# BLOCK3.net
KiCad netlist of a schematic drawn in Altium Designer
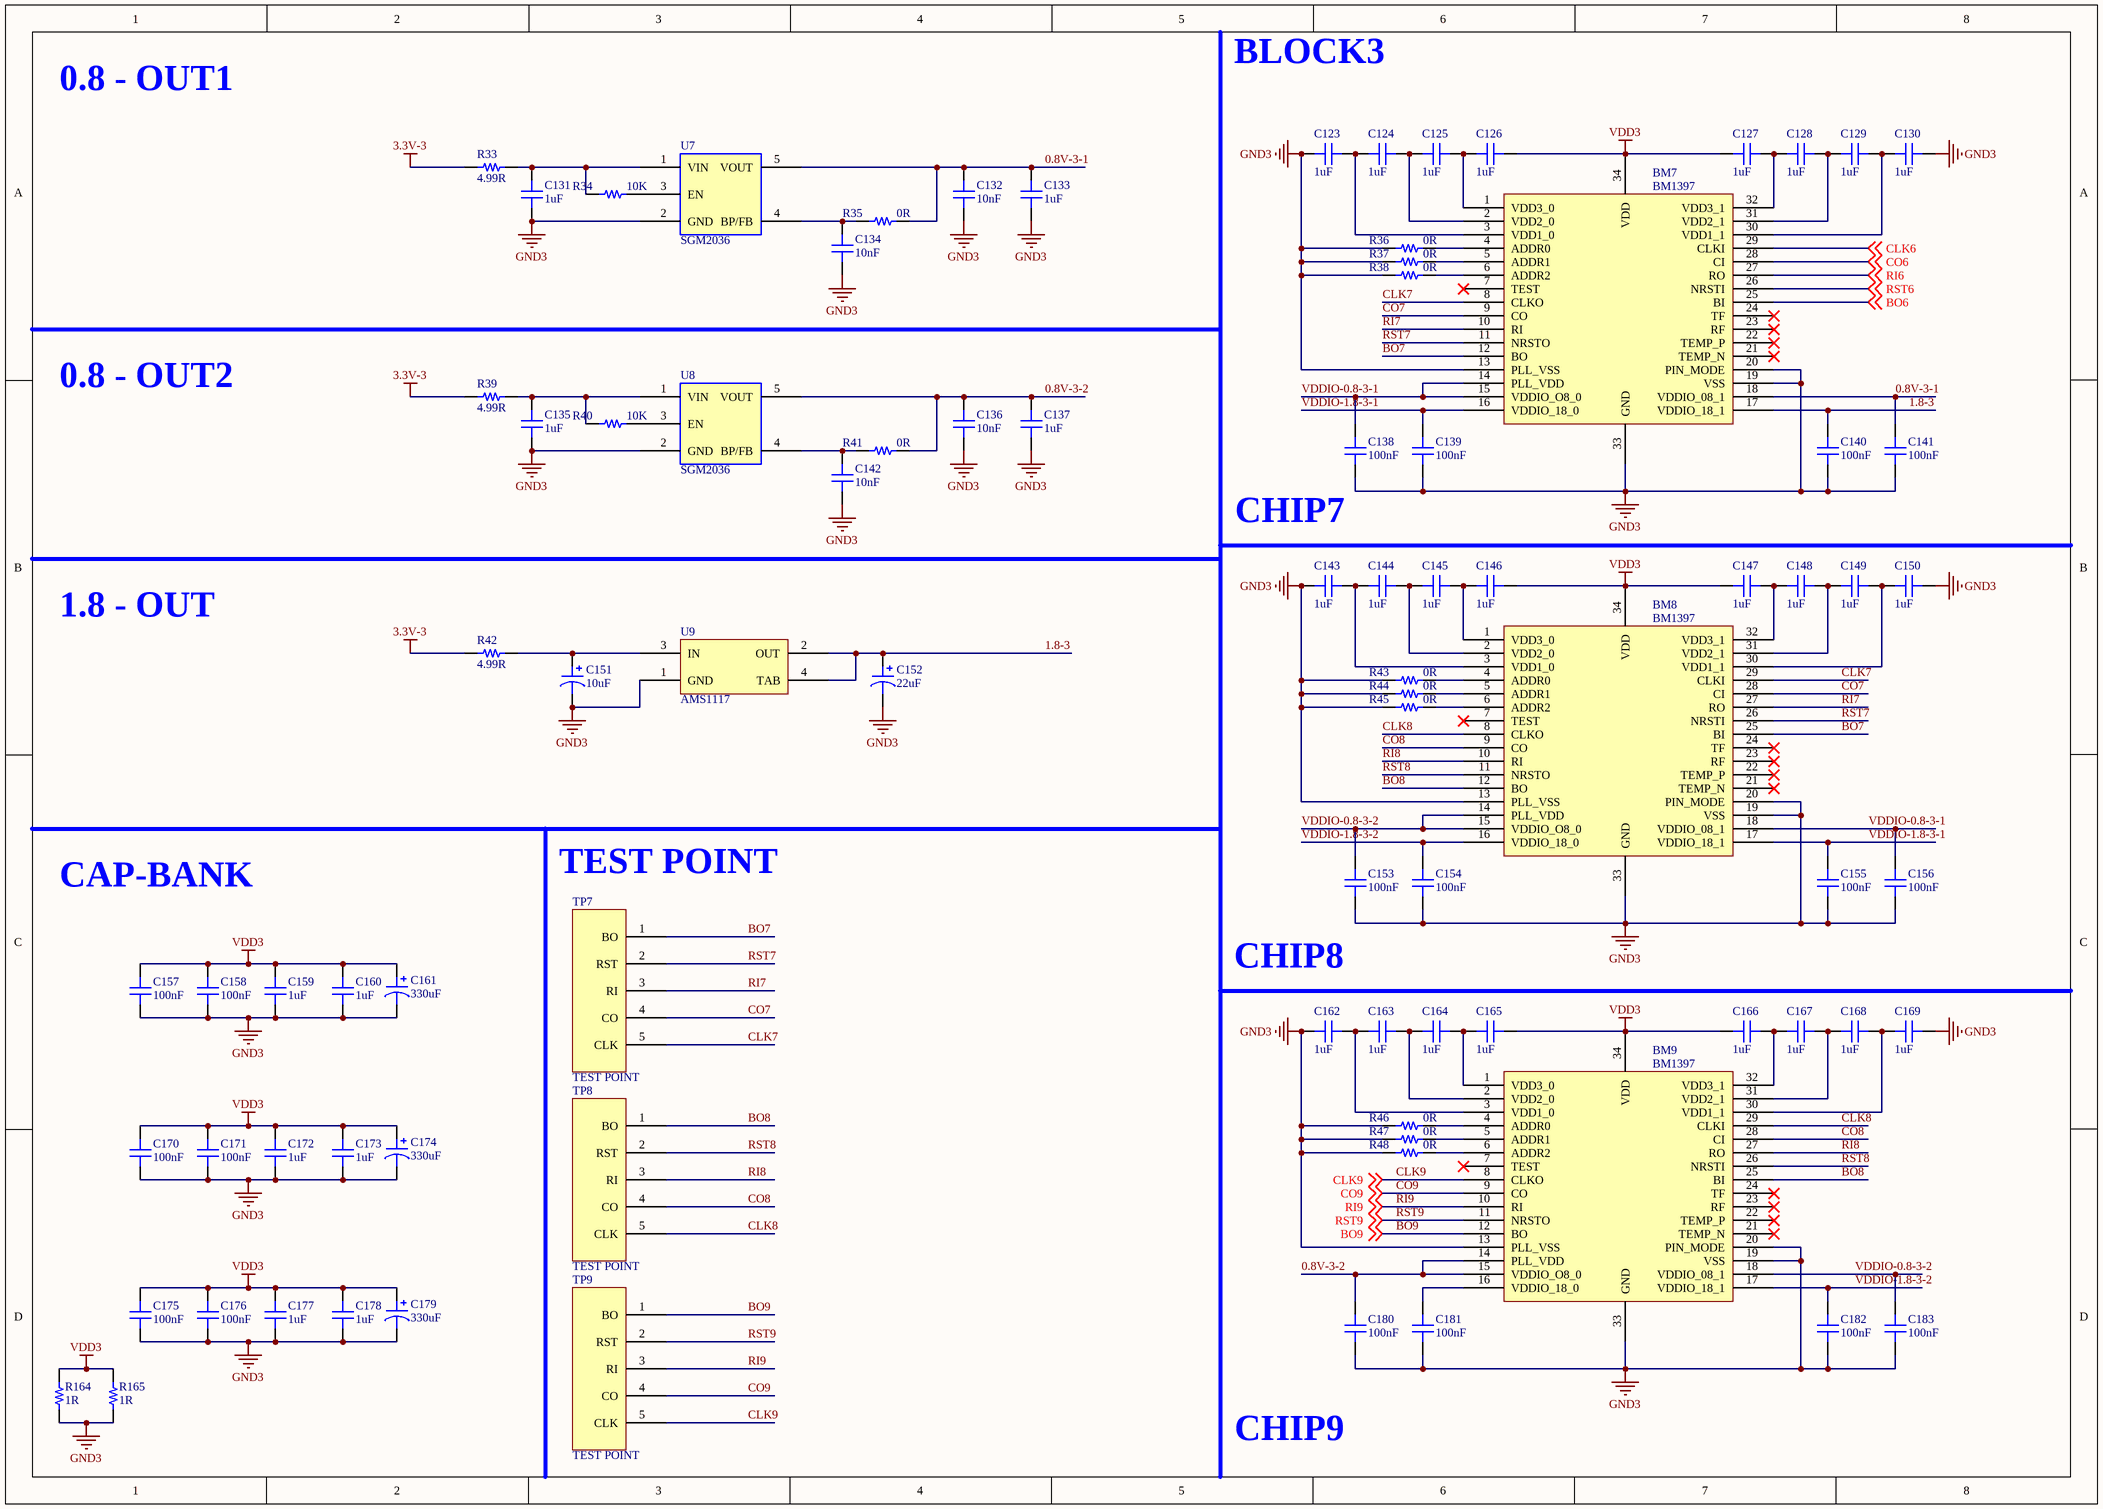
[diagram p0: BLOCK3.SchDoc]

(export (version "E")
  (design (tool "Eeschema 10.0.6"))
  (components
    (comp (ref "BM7") (value "BM1397") (footprint "BM1387") (libsource (lib "Miner_8TH") (part "BM1397_0")))
    (comp (ref "BM8") (value "BM1397") (footprint "BM1387") (libsource (lib "Miner_8TH") (part "BM1397_0")))
    (comp (ref "BM9") (value "BM1397") (footprint "BM1387") (libsource (lib "Miner_8TH") (part "BM1397_0")))
    (comp (ref "C123") (value "1uF") (footprint "CAP-SMD-0603") (libsource (lib "Miner_8TH") (part "CAP")))
    (comp (ref "C124") (value "1uF") (footprint "CAP-SMD-0603") (libsource (lib "Miner_8TH") (part "CAP")))
    (comp (ref "C125") (value "1uF") (footprint "CAP-SMD-0603") (libsource (lib "Miner_8TH") (part "CAP")))
    (comp (ref "C126") (value "1uF") (footprint "CAP-SMD-0603") (libsource (lib "Miner_8TH") (part "CAP")))
    (comp (ref "C127") (value "1uF") (footprint "CAP-SMD-0603") (libsource (lib "Miner_8TH") (part "CAP")))
    (comp (ref "C128") (value "1uF") (footprint "CAP-SMD-0603") (libsource (lib "Miner_8TH") (part "CAP")))
    (comp (ref "C129") (value "1uF") (footprint "CAP-SMD-0603") (libsource (lib "Miner_8TH") (part "CAP")))
    (comp (ref "C130") (value "1uF") (footprint "CAP-SMD-0603") (libsource (lib "Miner_8TH") (part "CAP")))
    (comp (ref "C131") (value "1uF") (footprint "CAP_SMD_0805") (libsource (lib "Miner_8TH") (part "CAP")))
    (comp (ref "C132") (value "10nF") (footprint "CAP_SMD_0805") (libsource (lib "Miner_8TH") (part "CAP")))
    (comp (ref "C133") (value "1uF") (footprint "CAP_SMD_0805") (libsource (lib "Miner_8TH") (part "CAP")))
    (comp (ref "C134") (value "10nF") (footprint "CAP_SMD_0805") (libsource (lib "Miner_8TH") (part "CAP")))
    (comp (ref "C135") (value "1uF") (footprint "CAP_SMD_0805") (libsource (lib "Miner_8TH") (part "CAP")))
    (comp (ref "C136") (value "10nF") (footprint "CAP_SMD_0805") (libsource (lib "Miner_8TH") (part "CAP")))
    (comp (ref "C137") (value "1uF") (footprint "CAP_SMD_0805") (libsource (lib "Miner_8TH") (part "CAP")))
    (comp (ref "C138") (value "100nF") (footprint "CAP_SMD_0805") (libsource (lib "Miner_8TH") (part "CAP")))
    (comp (ref "C139") (value "100nF") (footprint "CAP_SMD_0805") (libsource (lib "Miner_8TH") (part "CAP")))
    (comp (ref "C140") (value "100nF") (footprint "CAP_SMD_0805") (libsource (lib "Miner_8TH") (part "CAP")))
    (comp (ref "C141") (value "100nF") (footprint "CAP_SMD_0805") (libsource (lib "Miner_8TH") (part "CAP")))
    (comp (ref "C142") (value "10nF") (footprint "CAP_SMD_0805") (libsource (lib "Miner_8TH") (part "CAP")))
    (comp (ref "C143") (value "1uF") (footprint "CAP-SMD-0603") (libsource (lib "Miner_8TH") (part "CAP")))
    (comp (ref "C144") (value "1uF") (footprint "CAP-SMD-0603") (libsource (lib "Miner_8TH") (part "CAP")))
    (comp (ref "C145") (value "1uF") (footprint "CAP-SMD-0603") (libsource (lib "Miner_8TH") (part "CAP")))
    (comp (ref "C146") (value "1uF") (footprint "CAP-SMD-0603") (libsource (lib "Miner_8TH") (part "CAP")))
    (comp (ref "C147") (value "1uF") (footprint "CAP-SMD-0603") (libsource (lib "Miner_8TH") (part "CAP")))
    (comp (ref "C148") (value "1uF") (footprint "CAP-SMD-0603") (libsource (lib "Miner_8TH") (part "CAP")))
    (comp (ref "C149") (value "1uF") (footprint "CAP-SMD-0603") (libsource (lib "Miner_8TH") (part "CAP")))
    (comp (ref "C150") (value "1uF") (footprint "CAP-SMD-0603") (libsource (lib "Miner_8TH") (part "CAP")))
    (comp (ref "C151")
      (value "10uF")
      (footprint "CAP-TAN-CASE-A")
      (libsource (lib "Miner_8TH") (part "POLARIZED CAP"))
    )
    (comp (ref "C152")
      (value "22uF")
      (footprint "CAP-TAN-CASE-A")
      (libsource (lib "Miner_8TH") (part "POLARIZED CAP"))
    )
    (comp (ref "C153") (value "100nF") (footprint "CAP_SMD_0805") (libsource (lib "Miner_8TH") (part "CAP")))
    (comp (ref "C154") (value "100nF") (footprint "CAP_SMD_0805") (libsource (lib "Miner_8TH") (part "CAP")))
    (comp (ref "C155") (value "100nF") (footprint "CAP_SMD_0805") (libsource (lib "Miner_8TH") (part "CAP")))
    (comp (ref "C156") (value "100nF") (footprint "CAP_SMD_0805") (libsource (lib "Miner_8TH") (part "CAP")))
    (comp (ref "C157") (value "100nF") (footprint "CAP_SMD_0805") (libsource (lib "Miner_8TH") (part "CAP")))
    (comp (ref "C158") (value "100nF") (footprint "CAP_SMD_0805") (libsource (lib "Miner_8TH") (part "CAP")))
    (comp (ref "C159") (value "1uF") (footprint "CAP_SMD_0805") (libsource (lib "Miner_8TH") (part "CAP")))
    (comp (ref "C160") (value "1uF") (footprint "CAP_SMD_0805") (libsource (lib "Miner_8TH") (part "CAP")))
    (comp (ref "C161")
      (value "330uF")
      (footprint "CAP-TAN-CASE-E")
      (libsource (lib "Miner_8TH") (part "POLARIZED CAP"))
    )
    (comp (ref "C162") (value "1uF") (footprint "CAP-SMD-0603") (libsource (lib "Miner_8TH") (part "CAP")))
    (comp (ref "C163") (value "1uF") (footprint "CAP-SMD-0603") (libsource (lib "Miner_8TH") (part "CAP")))
    (comp (ref "C164") (value "1uF") (footprint "CAP-SMD-0603") (libsource (lib "Miner_8TH") (part "CAP")))
    (comp (ref "C165") (value "1uF") (footprint "CAP-SMD-0603") (libsource (lib "Miner_8TH") (part "CAP")))
    (comp (ref "C166") (value "1uF") (footprint "CAP-SMD-0603") (libsource (lib "Miner_8TH") (part "CAP")))
    (comp (ref "C167") (value "1uF") (footprint "CAP-SMD-0603") (libsource (lib "Miner_8TH") (part "CAP")))
    (comp (ref "C168") (value "1uF") (footprint "CAP-SMD-0603") (libsource (lib "Miner_8TH") (part "CAP")))
    (comp (ref "C169") (value "1uF") (footprint "CAP-SMD-0603") (libsource (lib "Miner_8TH") (part "CAP")))
    (comp (ref "C170") (value "100nF") (footprint "CAP_SMD_0805") (libsource (lib "Miner_8TH") (part "CAP")))
    (comp (ref "C171") (value "100nF") (footprint "CAP_SMD_0805") (libsource (lib "Miner_8TH") (part "CAP")))
    (comp (ref "C172") (value "1uF") (footprint "CAP_SMD_0805") (libsource (lib "Miner_8TH") (part "CAP")))
    (comp (ref "C173") (value "1uF") (footprint "CAP_SMD_0805") (libsource (lib "Miner_8TH") (part "CAP")))
    (comp (ref "C174")
      (value "330uF")
      (footprint "CAP-TAN-CASE-E")
      (libsource (lib "Miner_8TH") (part "POLARIZED CAP"))
    )
    (comp (ref "C175") (value "100nF") (footprint "CAP_SMD_0805") (libsource (lib "Miner_8TH") (part "CAP")))
    (comp (ref "C176") (value "100nF") (footprint "CAP_SMD_0805") (libsource (lib "Miner_8TH") (part "CAP")))
    (comp (ref "C177") (value "1uF") (footprint "CAP_SMD_0805") (libsource (lib "Miner_8TH") (part "CAP")))
    (comp (ref "C178") (value "1uF") (footprint "CAP_SMD_0805") (libsource (lib "Miner_8TH") (part "CAP")))
    (comp (ref "C179")
      (value "330uF")
      (footprint "CAP-TAN-CASE-E")
      (libsource (lib "Miner_8TH") (part "POLARIZED CAP"))
    )
    (comp (ref "C180") (value "100nF") (footprint "CAP_SMD_0805") (libsource (lib "Miner_8TH") (part "CAP")))
    (comp (ref "C181") (value "100nF") (footprint "CAP_SMD_0805") (libsource (lib "Miner_8TH") (part "CAP")))
    (comp (ref "C182") (value "100nF") (footprint "CAP_SMD_0805") (libsource (lib "Miner_8TH") (part "CAP")))
    (comp (ref "C183") (value "100nF") (footprint "CAP_SMD_0805") (libsource (lib "Miner_8TH") (part "CAP")))
    (comp (ref "R33") (value "4.99R") (footprint "RES-SMD-1206") (libsource (lib "Miner_8TH") (part "RES")))
    (comp (ref "R34") (value "10K") (footprint "RES-SMD-0402") (libsource (lib "Miner_8TH") (part "RES")))
    (comp (ref "R35") (value "0R") (footprint "RES-SMD-0402") (libsource (lib "Miner_8TH") (part "RES")))
    (comp (ref "R36") (value "0R") (footprint "RES-SMD-0402") (libsource (lib "Miner_8TH") (part "RES")))
    (comp (ref "R37") (value "0R") (footprint "RES-SMD-0402") (libsource (lib "Miner_8TH") (part "RES")))
    (comp (ref "R38") (value "0R") (footprint "RES-SMD-0402") (libsource (lib "Miner_8TH") (part "RES")))
    (comp (ref "R39") (value "4.99R") (footprint "RES-SMD-1206") (libsource (lib "Miner_8TH") (part "RES")))
    (comp (ref "R40") (value "10K") (footprint "RES-SMD-0402") (libsource (lib "Miner_8TH") (part "RES")))
    (comp (ref "R41") (value "0R") (footprint "RES-SMD-0402") (libsource (lib "Miner_8TH") (part "RES")))
    (comp (ref "R42") (value "4.99R") (footprint "RES-SMD-1206") (libsource (lib "Miner_8TH") (part "RES")))
    (comp (ref "R43") (value "0R") (footprint "RES-SMD-0402") (libsource (lib "Miner_8TH") (part "RES")))
    (comp (ref "R44") (value "0R") (footprint "RES-SMD-0402") (libsource (lib "Miner_8TH") (part "RES")))
    (comp (ref "R45") (value "0R") (footprint "RES-SMD-0402") (libsource (lib "Miner_8TH") (part "RES")))
    (comp (ref "R46") (value "0R") (footprint "RES-SMD-0402") (libsource (lib "Miner_8TH") (part "RES")))
    (comp (ref "R47") (value "0R") (footprint "RES-SMD-0402") (libsource (lib "Miner_8TH") (part "RES")))
    (comp (ref "R48") (value "0R") (footprint "RES-SMD-0402") (libsource (lib "Miner_8TH") (part "RES")))
    (comp (ref "R164") (value "1R") (footprint "RES-SMD-1210") (libsource (lib "Miner_8TH") (part "RES")))
    (comp (ref "R165") (value "1R") (footprint "RES-SMD-1210") (libsource (lib "Miner_8TH") (part "RES")))
    (comp (ref "TP7")
      (value "TEST POINT")
      (footprint "TEST_POINT")
      (libsource (lib "Miner_8TH") (part "TEST POINT"))
    )
    (comp (ref "TP8")
      (value "TEST POINT")
      (footprint "TEST_POINT")
      (libsource (lib "Miner_8TH") (part "TEST POINT"))
    )
    (comp (ref "TP9")
      (value "TEST POINT")
      (footprint "TEST_POINT")
      (libsource (lib "Miner_8TH") (part "TEST POINT"))
    )
    (comp (ref "U7")
      (value "SGM2036")
      (footprint "SOT23-5PIN")
      (libsource (lib "Miner_8TH") (part "SGM2036"))
    )
    (comp (ref "U8")
      (value "SGM2036")
      (footprint "SOT23-5PIN")
      (libsource (lib "Miner_8TH") (part "SGM2036"))
    )
    (comp (ref "U9") (value "AMS1117") (footprint "AMS1117") (libsource (lib "Miner_8TH") (part "AMS1117")))
  )
  (nets
    (net (code "1") (name "/0.8V-3-1") (class "Default")
      (node (ref "BM7") (pin "18") (pinfunction "VDDIO_08_1_18") (pintype "passive"))
      (node (ref "C132") (pin "2") (pinfunction "2_2") (pintype "passive"))
      (node (ref "C133") (pin "2") (pinfunction "2_2") (pintype "passive"))
      (node (ref "C141") (pin "2") (pinfunction "2_2") (pintype "passive"))
      (node (ref "R35") (pin "2") (pinfunction "2_2") (pintype "passive"))
      (node (ref "U7") (pin "5") (pinfunction "VOUT_5") (pintype "passive"))
    )
    (net (code "2") (name "/0.8V-3-2") (class "Default")
      (node (ref "BM9") (pin "14") (pinfunction "PLL_VDD_14") (pintype "passive"))
      (node (ref "BM9") (pin "15") (pinfunction "VDDIO_O8_0_15") (pintype "passive"))
      (node (ref "C136") (pin "2") (pinfunction "2_2") (pintype "passive"))
      (node (ref "C137") (pin "2") (pinfunction "2_2") (pintype "passive"))
      (node (ref "C180") (pin "2") (pinfunction "2_2") (pintype "passive"))
      (node (ref "R41") (pin "2") (pinfunction "2_2") (pintype "passive"))
      (node (ref "U8") (pin "5") (pinfunction "VOUT_5") (pintype "passive"))
    )
    (net (code "3") (name "/1.8-3") (class "Default")
      (node (ref "BM7") (pin "17") (pinfunction "VDDIO_18_1_17") (pintype "passive"))
      (node (ref "C140") (pin "2") (pinfunction "2_2") (pintype "passive"))
      (node (ref "C152") (pin "1") (pinfunction "1_1") (pintype "passive"))
      (node (ref "U9") (pin "2") (pinfunction "OUT_2") (pintype "passive"))
      (node (ref "U9") (pin "4") (pinfunction "TAB_4") (pintype "passive"))
    )
    (net (code "4") (name "/BO7") (class "Default")
      (node (ref "BM7") (pin "12") (pinfunction "BO_12") (pintype "passive"))
      (node (ref "BM8") (pin "25") (pinfunction "BI_25") (pintype "passive"))
      (node (ref "TP7") (pin "1") (pinfunction "BO_1") (pintype "passive"))
    )
    (net (code "5") (name "/BO8") (class "Default")
      (node (ref "BM8") (pin "12") (pinfunction "BO_12") (pintype "passive"))
      (node (ref "BM9") (pin "25") (pinfunction "BI_25") (pintype "passive"))
      (node (ref "TP8") (pin "1") (pinfunction "BO_1") (pintype "passive"))
    )
    (net (code "6") (name "/CLK7") (class "Default")
      (node (ref "BM7") (pin "8") (pinfunction "CLKO_8") (pintype "passive"))
      (node (ref "BM8") (pin "29") (pinfunction "CLKI_29") (pintype "passive"))
      (node (ref "TP7") (pin "5") (pinfunction "CLK_5") (pintype "passive"))
    )
    (net (code "7") (name "/CLK8") (class "Default")
      (node (ref "BM8") (pin "8") (pinfunction "CLKO_8") (pintype "passive"))
      (node (ref "BM9") (pin "29") (pinfunction "CLKI_29") (pintype "passive"))
      (node (ref "TP8") (pin "5") (pinfunction "CLK_5") (pintype "passive"))
    )
    (net (code "8") (name "/CO7") (class "Default")
      (node (ref "BM7") (pin "9") (pinfunction "CO_9") (pintype "passive"))
      (node (ref "BM8") (pin "28") (pinfunction "CI_28") (pintype "passive"))
      (node (ref "TP7") (pin "4") (pinfunction "CO_4") (pintype "passive"))
    )
    (net (code "9") (name "/CO8") (class "Default")
      (node (ref "BM8") (pin "9") (pinfunction "CO_9") (pintype "passive"))
      (node (ref "BM9") (pin "28") (pinfunction "CI_28") (pintype "passive"))
      (node (ref "TP8") (pin "4") (pinfunction "CO_4") (pintype "passive"))
    )
    (net (code "10") (name "/RI7") (class "Default")
      (node (ref "BM7") (pin "10") (pinfunction "RI_10") (pintype "passive"))
      (node (ref "BM8") (pin "27") (pinfunction "RO_27") (pintype "passive"))
      (node (ref "TP7") (pin "3") (pinfunction "RI_3") (pintype "passive"))
    )
    (net (code "11") (name "/RI8") (class "Default")
      (node (ref "BM8") (pin "10") (pinfunction "RI_10") (pintype "passive"))
      (node (ref "BM9") (pin "27") (pinfunction "RO_27") (pintype "passive"))
      (node (ref "TP8") (pin "3") (pinfunction "RI_3") (pintype "passive"))
    )
    (net (code "12") (name "/RST7") (class "Default")
      (node (ref "BM7") (pin "11") (pinfunction "NRSTO_11") (pintype "passive"))
      (node (ref "BM8") (pin "26") (pinfunction "NRSTI_26") (pintype "passive"))
      (node (ref "TP7") (pin "2") (pinfunction "RST_2") (pintype "passive"))
    )
    (net (code "13") (name "/RST8") (class "Default")
      (node (ref "BM8") (pin "11") (pinfunction "NRSTO_11") (pintype "passive"))
      (node (ref "BM9") (pin "26") (pinfunction "NRSTI_26") (pintype "passive"))
      (node (ref "TP8") (pin "2") (pinfunction "RST_2") (pintype "passive"))
    )
    (net (code "14") (name "/VDDIO-0.8-3-1") (class "Default")
      (node (ref "BM7") (pin "14") (pinfunction "PLL_VDD_14") (pintype "passive"))
      (node (ref "BM7") (pin "15") (pinfunction "VDDIO_O8_0_15") (pintype "passive"))
      (node (ref "BM8") (pin "18") (pinfunction "VDDIO_08_1_18") (pintype "passive"))
      (node (ref "C138") (pin "2") (pinfunction "2_2") (pintype "passive"))
      (node (ref "C156") (pin "2") (pinfunction "2_2") (pintype "passive"))
    )
    (net (code "15") (name "/VDDIO-0.8-3-2") (class "Default")
      (node (ref "BM8") (pin "14") (pinfunction "PLL_VDD_14") (pintype "passive"))
      (node (ref "BM8") (pin "15") (pinfunction "VDDIO_O8_0_15") (pintype "passive"))
      (node (ref "BM9") (pin "18") (pinfunction "VDDIO_08_1_18") (pintype "passive"))
      (node (ref "C153") (pin "2") (pinfunction "2_2") (pintype "passive"))
      (node (ref "C183") (pin "2") (pinfunction "2_2") (pintype "passive"))
    )
    (net (code "16") (name "/VDDIO-1.8-3-1") (class "Default")
      (node (ref "BM7") (pin "16") (pinfunction "VDDIO_18_0_16") (pintype "passive"))
      (node (ref "BM8") (pin "17") (pinfunction "VDDIO_18_1_17") (pintype "passive"))
      (node (ref "C139") (pin "2") (pinfunction "2_2") (pintype "passive"))
      (node (ref "C155") (pin "2") (pinfunction "2_2") (pintype "passive"))
    )
    (net (code "17") (name "/VDDIO-1.8-3-2") (class "Default")
      (node (ref "BM8") (pin "16") (pinfunction "VDDIO_18_0_16") (pintype "passive"))
      (node (ref "BM9") (pin "17") (pinfunction "VDDIO_18_1_17") (pintype "passive"))
      (node (ref "C154") (pin "2") (pinfunction "2_2") (pintype "passive"))
      (node (ref "C182") (pin "2") (pinfunction "2_2") (pintype "passive"))
    )
    (net (code "18") (name "3.3V-3") (class "Default")
      (node (ref "R33") (pin "1") (pinfunction "1_1") (pintype "passive"))
      (node (ref "R39") (pin "1") (pinfunction "1_1") (pintype "passive"))
      (node (ref "R42") (pin "1") (pinfunction "1_1") (pintype "passive"))
    )
    (net (code "19") (name "BO6") (class "Default")
      (node (ref "BM7") (pin "25") (pinfunction "BI_25") (pintype "passive"))
    )
    (net (code "20") (name "BO9") (class "Default")
      (node (ref "BM9") (pin "12") (pinfunction "BO_12") (pintype "passive"))
      (node (ref "TP9") (pin "1") (pinfunction "BO_1") (pintype "passive"))
    )
    (net (code "21") (name "CLK6") (class "Default")
      (node (ref "BM7") (pin "29") (pinfunction "CLKI_29") (pintype "passive"))
    )
    (net (code "22") (name "CLK9") (class "Default")
      (node (ref "BM9") (pin "8") (pinfunction "CLKO_8") (pintype "passive"))
      (node (ref "TP9") (pin "5") (pinfunction "CLK_5") (pintype "passive"))
    )
    (net (code "23") (name "CO6") (class "Default")
      (node (ref "BM7") (pin "28") (pinfunction "CI_28") (pintype "passive"))
    )
    (net (code "24") (name "CO9") (class "Default")
      (node (ref "BM9") (pin "9") (pinfunction "CO_9") (pintype "passive"))
      (node (ref "TP9") (pin "4") (pinfunction "CO_4") (pintype "passive"))
    )
    (net (code "25") (name "GND3") (class "Default")
      (node (ref "BM7") (pin "13") (pinfunction "PLL_VSS_13") (pintype "passive"))
      (node (ref "BM7") (pin "19") (pinfunction "VSS_19") (pintype "passive"))
      (node (ref "BM7") (pin "20") (pinfunction "PIN_MODE_20") (pintype "passive"))
      (node (ref "BM7") (pin "33") (pinfunction "GND_33") (pintype "passive"))
      (node (ref "BM8") (pin "13") (pinfunction "PLL_VSS_13") (pintype "passive"))
      (node (ref "BM8") (pin "19") (pinfunction "VSS_19") (pintype "passive"))
      (node (ref "BM8") (pin "20") (pinfunction "PIN_MODE_20") (pintype "passive"))
      (node (ref "BM8") (pin "33") (pinfunction "GND_33") (pintype "passive"))
      (node (ref "BM9") (pin "13") (pinfunction "PLL_VSS_13") (pintype "passive"))
      (node (ref "BM9") (pin "19") (pinfunction "VSS_19") (pintype "passive"))
      (node (ref "BM9") (pin "20") (pinfunction "PIN_MODE_20") (pintype "passive"))
      (node (ref "BM9") (pin "33") (pinfunction "GND_33") (pintype "passive"))
      (node (ref "C123") (pin "1") (pinfunction "1_1") (pintype "passive"))
      (node (ref "C130") (pin "2") (pinfunction "2_2") (pintype "passive"))
      (node (ref "C131") (pin "1") (pinfunction "1_1") (pintype "passive"))
      (node (ref "C132") (pin "1") (pinfunction "1_1") (pintype "passive"))
      (node (ref "C133") (pin "1") (pinfunction "1_1") (pintype "passive"))
      (node (ref "C134") (pin "1") (pinfunction "1_1") (pintype "passive"))
      (node (ref "C135") (pin "1") (pinfunction "1_1") (pintype "passive"))
      (node (ref "C136") (pin "1") (pinfunction "1_1") (pintype "passive"))
      (node (ref "C137") (pin "1") (pinfunction "1_1") (pintype "passive"))
      (node (ref "C138") (pin "1") (pinfunction "1_1") (pintype "passive"))
      (node (ref "C139") (pin "1") (pinfunction "1_1") (pintype "passive"))
      (node (ref "C140") (pin "1") (pinfunction "1_1") (pintype "passive"))
      (node (ref "C141") (pin "1") (pinfunction "1_1") (pintype "passive"))
      (node (ref "C142") (pin "1") (pinfunction "1_1") (pintype "passive"))
      (node (ref "C143") (pin "1") (pinfunction "1_1") (pintype "passive"))
      (node (ref "C150") (pin "2") (pinfunction "2_2") (pintype "passive"))
      (node (ref "C151") (pin "2") (pinfunction "2_2") (pintype "passive"))
      (node (ref "C152") (pin "2") (pinfunction "2_2") (pintype "passive"))
      (node (ref "C153") (pin "1") (pinfunction "1_1") (pintype "passive"))
      (node (ref "C154") (pin "1") (pinfunction "1_1") (pintype "passive"))
      (node (ref "C155") (pin "1") (pinfunction "1_1") (pintype "passive"))
      (node (ref "C156") (pin "1") (pinfunction "1_1") (pintype "passive"))
      (node (ref "C157") (pin "1") (pinfunction "1_1") (pintype "passive"))
      (node (ref "C158") (pin "1") (pinfunction "1_1") (pintype "passive"))
      (node (ref "C159") (pin "1") (pinfunction "1_1") (pintype "passive"))
      (node (ref "C160") (pin "1") (pinfunction "1_1") (pintype "passive"))
      (node (ref "C161") (pin "2") (pinfunction "2_2") (pintype "passive"))
      (node (ref "C162") (pin "1") (pinfunction "1_1") (pintype "passive"))
      (node (ref "C169") (pin "2") (pinfunction "2_2") (pintype "passive"))
      (node (ref "C170") (pin "1") (pinfunction "1_1") (pintype "passive"))
      (node (ref "C171") (pin "1") (pinfunction "1_1") (pintype "passive"))
      (node (ref "C172") (pin "1") (pinfunction "1_1") (pintype "passive"))
      (node (ref "C173") (pin "1") (pinfunction "1_1") (pintype "passive"))
      (node (ref "C174") (pin "2") (pinfunction "2_2") (pintype "passive"))
      (node (ref "C175") (pin "1") (pinfunction "1_1") (pintype "passive"))
      (node (ref "C176") (pin "1") (pinfunction "1_1") (pintype "passive"))
      (node (ref "C177") (pin "1") (pinfunction "1_1") (pintype "passive"))
      (node (ref "C178") (pin "1") (pinfunction "1_1") (pintype "passive"))
      (node (ref "C179") (pin "2") (pinfunction "2_2") (pintype "passive"))
      (node (ref "C180") (pin "1") (pinfunction "1_1") (pintype "passive"))
      (node (ref "C181") (pin "1") (pinfunction "1_1") (pintype "passive"))
      (node (ref "C182") (pin "1") (pinfunction "1_1") (pintype "passive"))
      (node (ref "C183") (pin "1") (pinfunction "1_1") (pintype "passive"))
      (node (ref "R164") (pin "1") (pinfunction "1_1") (pintype "passive"))
      (node (ref "R165") (pin "1") (pinfunction "1_1") (pintype "passive"))
      (node (ref "R36") (pin "1") (pinfunction "1_1") (pintype "passive"))
      (node (ref "R37") (pin "1") (pinfunction "1_1") (pintype "passive"))
      (node (ref "R38") (pin "1") (pinfunction "1_1") (pintype "passive"))
      (node (ref "R43") (pin "1") (pinfunction "1_1") (pintype "passive"))
      (node (ref "R44") (pin "1") (pinfunction "1_1") (pintype "passive"))
      (node (ref "R45") (pin "1") (pinfunction "1_1") (pintype "passive"))
      (node (ref "R46") (pin "1") (pinfunction "1_1") (pintype "passive"))
      (node (ref "R47") (pin "1") (pinfunction "1_1") (pintype "passive"))
      (node (ref "R48") (pin "1") (pinfunction "1_1") (pintype "passive"))
      (node (ref "U7") (pin "2") (pinfunction "GND_2") (pintype "passive"))
      (node (ref "U8") (pin "2") (pinfunction "GND_2") (pintype "passive"))
      (node (ref "U9") (pin "1") (pinfunction "GND_1") (pintype "passive"))
    )
    (net (code "26") (name "Net-(BM7-ADDR0)") (class "Default")
      (node (ref "BM7") (pin "4") (pinfunction "ADDR0_4") (pintype "passive"))
      (node (ref "R36") (pin "2") (pinfunction "2_2") (pintype "passive"))
    )
    (net (code "27") (name "Net-(BM7-ADDR1)") (class "Default")
      (node (ref "BM7") (pin "5") (pinfunction "ADDR1_5") (pintype "passive"))
      (node (ref "R37") (pin "2") (pinfunction "2_2") (pintype "passive"))
    )
    (net (code "28") (name "Net-(BM7-ADDR2)") (class "Default")
      (node (ref "BM7") (pin "6") (pinfunction "ADDR2_6") (pintype "passive"))
      (node (ref "R38") (pin "2") (pinfunction "2_2") (pintype "passive"))
    )
    (net (code "29") (name "Net-(BM7-VDD1_0)") (class "Default")
      (node (ref "BM7") (pin "3") (pinfunction "VDD1_0_3") (pintype "passive"))
      (node (ref "C123") (pin "2") (pinfunction "2_2") (pintype "passive"))
      (node (ref "C124") (pin "1") (pinfunction "1_1") (pintype "passive"))
    )
    (net (code "30") (name "Net-(BM7-VDD1_1)") (class "Default")
      (node (ref "BM7") (pin "30") (pinfunction "VDD1_1_30") (pintype "passive"))
      (node (ref "C129") (pin "2") (pinfunction "2_2") (pintype "passive"))
      (node (ref "C130") (pin "1") (pinfunction "1_1") (pintype "passive"))
    )
    (net (code "31") (name "Net-(BM7-VDD2_0)") (class "Default")
      (node (ref "BM7") (pin "2") (pinfunction "VDD2_0_2") (pintype "passive"))
      (node (ref "C124") (pin "2") (pinfunction "2_2") (pintype "passive"))
      (node (ref "C125") (pin "1") (pinfunction "1_1") (pintype "passive"))
    )
    (net (code "32") (name "Net-(BM7-VDD2_1)") (class "Default")
      (node (ref "BM7") (pin "31") (pinfunction "VDD2_1_31") (pintype "passive"))
      (node (ref "C128") (pin "2") (pinfunction "2_2") (pintype "passive"))
      (node (ref "C129") (pin "1") (pinfunction "1_1") (pintype "passive"))
    )
    (net (code "33") (name "Net-(BM7-VDD3_0)") (class "Default")
      (node (ref "BM7") (pin "1") (pinfunction "VDD3_0_1") (pintype "passive"))
      (node (ref "C125") (pin "2") (pinfunction "2_2") (pintype "passive"))
      (node (ref "C126") (pin "1") (pinfunction "1_1") (pintype "passive"))
    )
    (net (code "34") (name "Net-(BM7-VDD3_1)") (class "Default")
      (node (ref "BM7") (pin "32") (pinfunction "VDD3_1_32") (pintype "passive"))
      (node (ref "C127") (pin "2") (pinfunction "2_2") (pintype "passive"))
      (node (ref "C128") (pin "1") (pinfunction "1_1") (pintype "passive"))
    )
    (net (code "35") (name "Net-(BM8-ADDR0)") (class "Default")
      (node (ref "BM8") (pin "4") (pinfunction "ADDR0_4") (pintype "passive"))
      (node (ref "R43") (pin "2") (pinfunction "2_2") (pintype "passive"))
    )
    (net (code "36") (name "Net-(BM8-ADDR1)") (class "Default")
      (node (ref "BM8") (pin "5") (pinfunction "ADDR1_5") (pintype "passive"))
      (node (ref "R44") (pin "2") (pinfunction "2_2") (pintype "passive"))
    )
    (net (code "37") (name "Net-(BM8-ADDR2)") (class "Default")
      (node (ref "BM8") (pin "6") (pinfunction "ADDR2_6") (pintype "passive"))
      (node (ref "R45") (pin "2") (pinfunction "2_2") (pintype "passive"))
    )
    (net (code "38") (name "Net-(BM8-VDD1_0)") (class "Default")
      (node (ref "BM8") (pin "3") (pinfunction "VDD1_0_3") (pintype "passive"))
      (node (ref "C143") (pin "2") (pinfunction "2_2") (pintype "passive"))
      (node (ref "C144") (pin "1") (pinfunction "1_1") (pintype "passive"))
    )
    (net (code "39") (name "Net-(BM8-VDD1_1)") (class "Default")
      (node (ref "BM8") (pin "30") (pinfunction "VDD1_1_30") (pintype "passive"))
      (node (ref "C149") (pin "2") (pinfunction "2_2") (pintype "passive"))
      (node (ref "C150") (pin "1") (pinfunction "1_1") (pintype "passive"))
    )
    (net (code "40") (name "Net-(BM8-VDD2_0)") (class "Default")
      (node (ref "BM8") (pin "2") (pinfunction "VDD2_0_2") (pintype "passive"))
      (node (ref "C144") (pin "2") (pinfunction "2_2") (pintype "passive"))
      (node (ref "C145") (pin "1") (pinfunction "1_1") (pintype "passive"))
    )
    (net (code "41") (name "Net-(BM8-VDD2_1)") (class "Default")
      (node (ref "BM8") (pin "31") (pinfunction "VDD2_1_31") (pintype "passive"))
      (node (ref "C148") (pin "2") (pinfunction "2_2") (pintype "passive"))
      (node (ref "C149") (pin "1") (pinfunction "1_1") (pintype "passive"))
    )
    (net (code "42") (name "Net-(BM8-VDD3_0)") (class "Default")
      (node (ref "BM8") (pin "1") (pinfunction "VDD3_0_1") (pintype "passive"))
      (node (ref "C145") (pin "2") (pinfunction "2_2") (pintype "passive"))
      (node (ref "C146") (pin "1") (pinfunction "1_1") (pintype "passive"))
    )
    (net (code "43") (name "Net-(BM8-VDD3_1)") (class "Default")
      (node (ref "BM8") (pin "32") (pinfunction "VDD3_1_32") (pintype "passive"))
      (node (ref "C147") (pin "2") (pinfunction "2_2") (pintype "passive"))
      (node (ref "C148") (pin "1") (pinfunction "1_1") (pintype "passive"))
    )
    (net (code "44") (name "Net-(BM9-ADDR0)") (class "Default")
      (node (ref "BM9") (pin "4") (pinfunction "ADDR0_4") (pintype "passive"))
      (node (ref "R46") (pin "2") (pinfunction "2_2") (pintype "passive"))
    )
    (net (code "45") (name "Net-(BM9-ADDR1)") (class "Default")
      (node (ref "BM9") (pin "5") (pinfunction "ADDR1_5") (pintype "passive"))
      (node (ref "R47") (pin "2") (pinfunction "2_2") (pintype "passive"))
    )
    (net (code "46") (name "Net-(BM9-ADDR2)") (class "Default")
      (node (ref "BM9") (pin "6") (pinfunction "ADDR2_6") (pintype "passive"))
      (node (ref "R48") (pin "2") (pinfunction "2_2") (pintype "passive"))
    )
    (net (code "47") (name "Net-(BM9-VDD1_0)") (class "Default")
      (node (ref "BM9") (pin "3") (pinfunction "VDD1_0_3") (pintype "passive"))
      (node (ref "C162") (pin "2") (pinfunction "2_2") (pintype "passive"))
      (node (ref "C163") (pin "1") (pinfunction "1_1") (pintype "passive"))
    )
    (net (code "48") (name "Net-(BM9-VDD1_1)") (class "Default")
      (node (ref "BM9") (pin "30") (pinfunction "VDD1_1_30") (pintype "passive"))
      (node (ref "C168") (pin "2") (pinfunction "2_2") (pintype "passive"))
      (node (ref "C169") (pin "1") (pinfunction "1_1") (pintype "passive"))
    )
    (net (code "49") (name "Net-(BM9-VDD2_0)") (class "Default")
      (node (ref "BM9") (pin "2") (pinfunction "VDD2_0_2") (pintype "passive"))
      (node (ref "C163") (pin "2") (pinfunction "2_2") (pintype "passive"))
      (node (ref "C164") (pin "1") (pinfunction "1_1") (pintype "passive"))
    )
    (net (code "50") (name "Net-(BM9-VDD2_1)") (class "Default")
      (node (ref "BM9") (pin "31") (pinfunction "VDD2_1_31") (pintype "passive"))
      (node (ref "C167") (pin "2") (pinfunction "2_2") (pintype "passive"))
      (node (ref "C168") (pin "1") (pinfunction "1_1") (pintype "passive"))
    )
    (net (code "51") (name "Net-(BM9-VDD3_0)") (class "Default")
      (node (ref "BM9") (pin "1") (pinfunction "VDD3_0_1") (pintype "passive"))
      (node (ref "C164") (pin "2") (pinfunction "2_2") (pintype "passive"))
      (node (ref "C165") (pin "1") (pinfunction "1_1") (pintype "passive"))
    )
    (net (code "52") (name "Net-(BM9-VDD3_1)") (class "Default")
      (node (ref "BM9") (pin "32") (pinfunction "VDD3_1_32") (pintype "passive"))
      (node (ref "C166") (pin "2") (pinfunction "2_2") (pintype "passive"))
      (node (ref "C167") (pin "1") (pinfunction "1_1") (pintype "passive"))
    )
    (net (code "53") (name "Net-(BM9-VDDIO_18_0)") (class "Default")
      (node (ref "BM9") (pin "16") (pinfunction "VDDIO_18_0_16") (pintype "passive"))
      (node (ref "C181") (pin "2") (pinfunction "2_2") (pintype "passive"))
    )
    (net (code "54") (name "Net-(U7-BP{slash}FB)") (class "Default")
      (node (ref "C134") (pin "2") (pinfunction "2_2") (pintype "passive"))
      (node (ref "R35") (pin "1") (pinfunction "1_1") (pintype "passive"))
      (node (ref "U7") (pin "4") (pinfunction "BP/FB_4") (pintype "passive"))
    )
    (net (code "55") (name "Net-(U7-EN)") (class "Default")
      (node (ref "R34") (pin "2") (pinfunction "2_2") (pintype "passive"))
      (node (ref "U7") (pin "3") (pinfunction "EN_3") (pintype "passive"))
    )
    (net (code "56") (name "Net-(U7-VIN)") (class "Default")
      (node (ref "C131") (pin "2") (pinfunction "2_2") (pintype "passive"))
      (node (ref "R33") (pin "2") (pinfunction "2_2") (pintype "passive"))
      (node (ref "R34") (pin "1") (pinfunction "1_1") (pintype "passive"))
      (node (ref "U7") (pin "1") (pinfunction "VIN_1") (pintype "passive"))
    )
    (net (code "57") (name "Net-(U8-BP{slash}FB)") (class "Default")
      (node (ref "C142") (pin "2") (pinfunction "2_2") (pintype "passive"))
      (node (ref "R41") (pin "1") (pinfunction "1_1") (pintype "passive"))
      (node (ref "U8") (pin "4") (pinfunction "BP/FB_4") (pintype "passive"))
    )
    (net (code "58") (name "Net-(U8-EN)") (class "Default")
      (node (ref "R40") (pin "2") (pinfunction "2_2") (pintype "passive"))
      (node (ref "U8") (pin "3") (pinfunction "EN_3") (pintype "passive"))
    )
    (net (code "59") (name "Net-(U8-VIN)") (class "Default")
      (node (ref "C135") (pin "2") (pinfunction "2_2") (pintype "passive"))
      (node (ref "R39") (pin "2") (pinfunction "2_2") (pintype "passive"))
      (node (ref "R40") (pin "1") (pinfunction "1_1") (pintype "passive"))
      (node (ref "U8") (pin "1") (pinfunction "VIN_1") (pintype "passive"))
    )
    (net (code "60") (name "Net-(U9-IN)") (class "Default")
      (node (ref "C151") (pin "1") (pinfunction "1_1") (pintype "passive"))
      (node (ref "R42") (pin "2") (pinfunction "2_2") (pintype "passive"))
      (node (ref "U9") (pin "3") (pinfunction "IN_3") (pintype "passive"))
    )
    (net (code "61") (name "RI6") (class "Default")
      (node (ref "BM7") (pin "27") (pinfunction "RO_27") (pintype "passive"))
    )
    (net (code "62") (name "RI9") (class "Default")
      (node (ref "BM9") (pin "10") (pinfunction "RI_10") (pintype "passive"))
      (node (ref "TP9") (pin "3") (pinfunction "RI_3") (pintype "passive"))
    )
    (net (code "63") (name "RST6") (class "Default")
      (node (ref "BM7") (pin "26") (pinfunction "NRSTI_26") (pintype "passive"))
    )
    (net (code "64") (name "RST9") (class "Default")
      (node (ref "BM9") (pin "11") (pinfunction "NRSTO_11") (pintype "passive"))
      (node (ref "TP9") (pin "2") (pinfunction "RST_2") (pintype "passive"))
    )
    (net (code "65") (name "VDD3") (class "Default")
      (node (ref "BM7") (pin "34") (pinfunction "VDD_34") (pintype "passive"))
      (node (ref "BM8") (pin "34") (pinfunction "VDD_34") (pintype "passive"))
      (node (ref "BM9") (pin "34") (pinfunction "VDD_34") (pintype "passive"))
      (node (ref "C126") (pin "2") (pinfunction "2_2") (pintype "passive"))
      (node (ref "C127") (pin "1") (pinfunction "1_1") (pintype "passive"))
      (node (ref "C146") (pin "2") (pinfunction "2_2") (pintype "passive"))
      (node (ref "C147") (pin "1") (pinfunction "1_1") (pintype "passive"))
      (node (ref "C157") (pin "2") (pinfunction "2_2") (pintype "passive"))
      (node (ref "C158") (pin "2") (pinfunction "2_2") (pintype "passive"))
      (node (ref "C159") (pin "2") (pinfunction "2_2") (pintype "passive"))
      (node (ref "C160") (pin "2") (pinfunction "2_2") (pintype "passive"))
      (node (ref "C161") (pin "1") (pinfunction "1_1") (pintype "passive"))
      (node (ref "C165") (pin "2") (pinfunction "2_2") (pintype "passive"))
      (node (ref "C166") (pin "1") (pinfunction "1_1") (pintype "passive"))
      (node (ref "C170") (pin "2") (pinfunction "2_2") (pintype "passive"))
      (node (ref "C171") (pin "2") (pinfunction "2_2") (pintype "passive"))
      (node (ref "C172") (pin "2") (pinfunction "2_2") (pintype "passive"))
      (node (ref "C173") (pin "2") (pinfunction "2_2") (pintype "passive"))
      (node (ref "C174") (pin "1") (pinfunction "1_1") (pintype "passive"))
      (node (ref "C175") (pin "2") (pinfunction "2_2") (pintype "passive"))
      (node (ref "C176") (pin "2") (pinfunction "2_2") (pintype "passive"))
      (node (ref "C177") (pin "2") (pinfunction "2_2") (pintype "passive"))
      (node (ref "C178") (pin "2") (pinfunction "2_2") (pintype "passive"))
      (node (ref "C179") (pin "1") (pinfunction "1_1") (pintype "passive"))
      (node (ref "R164") (pin "2") (pinfunction "2_2") (pintype "passive"))
      (node (ref "R165") (pin "2") (pinfunction "2_2") (pintype "passive"))
    )
    (net (code "66") (name "unconnected-(BM7-RF-Pad23)") (class "Default")
      (node (ref "BM7") (pin "23") (pinfunction "RF_23") (pintype "passive+no_connect"))
    )
    (net (code "67") (name "unconnected-(BM7-TEMP_N-Pad21)") (class "Default")
      (node (ref "BM7") (pin "21") (pinfunction "TEMP_N_21") (pintype "passive+no_connect"))
    )
    (net (code "68") (name "unconnected-(BM7-TEMP_P-Pad22)") (class "Default")
      (node (ref "BM7") (pin "22") (pinfunction "TEMP_P_22") (pintype "passive+no_connect"))
    )
    (net (code "69") (name "unconnected-(BM7-TEST-Pad7)") (class "Default")
      (node (ref "BM7") (pin "7") (pinfunction "TEST_7") (pintype "passive+no_connect"))
    )
    (net (code "70") (name "unconnected-(BM7-TF-Pad24)") (class "Default")
      (node (ref "BM7") (pin "24") (pinfunction "TF_24") (pintype "passive+no_connect"))
    )
    (net (code "71") (name "unconnected-(BM8-RF-Pad23)") (class "Default")
      (node (ref "BM8") (pin "23") (pinfunction "RF_23") (pintype "passive+no_connect"))
    )
    (net (code "72") (name "unconnected-(BM8-TEMP_N-Pad21)") (class "Default")
      (node (ref "BM8") (pin "21") (pinfunction "TEMP_N_21") (pintype "passive+no_connect"))
    )
    (net (code "73") (name "unconnected-(BM8-TEMP_P-Pad22)") (class "Default")
      (node (ref "BM8") (pin "22") (pinfunction "TEMP_P_22") (pintype "passive+no_connect"))
    )
    (net (code "74") (name "unconnected-(BM8-TEST-Pad7)") (class "Default")
      (node (ref "BM8") (pin "7") (pinfunction "TEST_7") (pintype "passive+no_connect"))
    )
    (net (code "75") (name "unconnected-(BM8-TF-Pad24)") (class "Default")
      (node (ref "BM8") (pin "24") (pinfunction "TF_24") (pintype "passive+no_connect"))
    )
    (net (code "76") (name "unconnected-(BM9-RF-Pad23)") (class "Default")
      (node (ref "BM9") (pin "23") (pinfunction "RF_23") (pintype "passive+no_connect"))
    )
    (net (code "77") (name "unconnected-(BM9-TEMP_N-Pad21)") (class "Default")
      (node (ref "BM9") (pin "21") (pinfunction "TEMP_N_21") (pintype "passive+no_connect"))
    )
    (net (code "78") (name "unconnected-(BM9-TEMP_P-Pad22)") (class "Default")
      (node (ref "BM9") (pin "22") (pinfunction "TEMP_P_22") (pintype "passive+no_connect"))
    )
    (net (code "79") (name "unconnected-(BM9-TEST-Pad7)") (class "Default")
      (node (ref "BM9") (pin "7") (pinfunction "TEST_7") (pintype "passive+no_connect"))
    )
    (net (code "80") (name "unconnected-(BM9-TF-Pad24)") (class "Default")
      (node (ref "BM9") (pin "24") (pinfunction "TF_24") (pintype "passive+no_connect"))
    )
  )
)
